# RevA.net
KiCad netlist of a schematic drawn in EAGLE
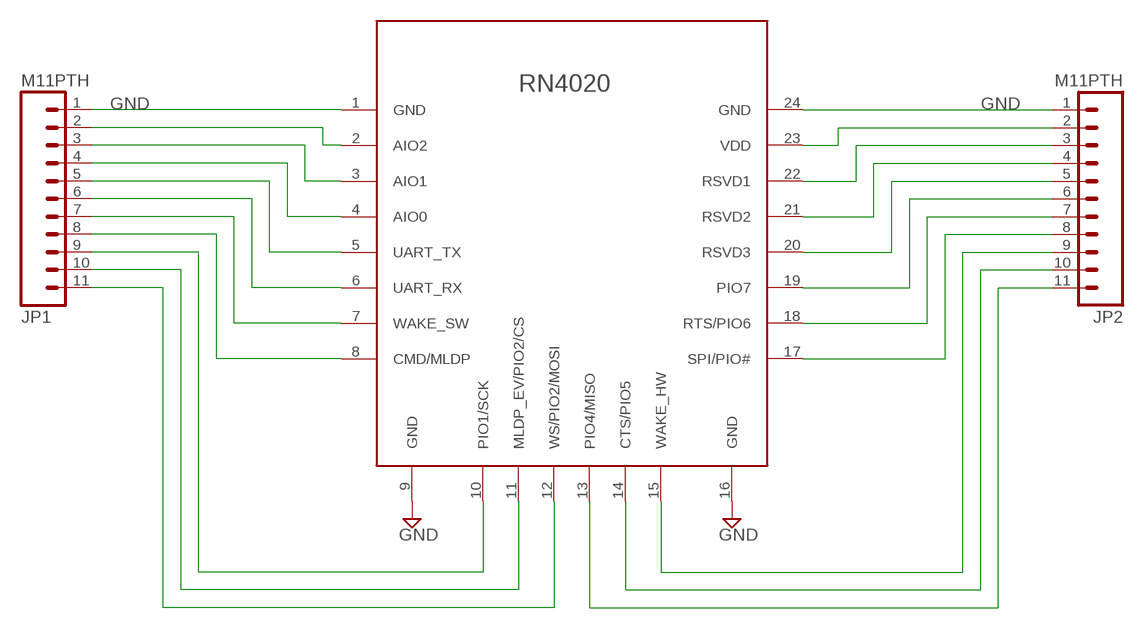
[diagram p0: schematic, sheet 1]

(export (version "E")
  (design (tool "Eeschema 10.0.6"))
  (components
    (comp (ref "JP1")
      (value "M11PTH")
      (footprint "eagle-import:1X11")
      (libsource (lib "eagle-import") (part "M11PTH"))
    )
    (comp (ref "JP2")
      (value "M11PTH")
      (footprint "eagle-import:1X11")
      (libsource (lib "eagle-import") (part "M11PTH"))
    )
    (comp (ref "U$1")
      (value "RN4020")
      (footprint "eagle-import:RN4020")
      (libsource (lib "eagle-import") (part "RN4020"))
    )
  )
  (nets
    (net (code "1") (name "GND") (class "Default")
      (node (ref "JP1") (pin "1") (pinfunction "1_1") (pintype "passive"))
      (node (ref "JP2") (pin "1") (pinfunction "1_1") (pintype "passive"))
      (node (ref "U$1") (pin "1") (pinfunction "GND_1") (pintype "power_in"))
      (node (ref "U$1") (pin "16") (pinfunction "GND_16") (pintype "power_in"))
      (node (ref "U$1") (pin "24") (pinfunction "GND_24") (pintype "power_in"))
      (node (ref "U$1") (pin "9") (pinfunction "GND_9") (pintype "power_in"))
    )
    (net (code "2") (name "Net-(U$1-AIO0)") (class "Default")
      (node (ref "JP1") (pin "4") (pinfunction "4_4") (pintype "passive"))
      (node (ref "U$1") (pin "4") (pinfunction "AIO0_4") (pintype "bidirectional"))
    )
    (net (code "3") (name "Net-(U$1-AIO1)") (class "Default")
      (node (ref "JP1") (pin "3") (pinfunction "3_3") (pintype "passive"))
      (node (ref "U$1") (pin "3") (pinfunction "AIO1_3") (pintype "bidirectional"))
    )
    (net (code "4") (name "Net-(U$1-AIO2)") (class "Default")
      (node (ref "JP1") (pin "2") (pinfunction "2_2") (pintype "passive"))
      (node (ref "U$1") (pin "2") (pinfunction "AIO2_2") (pintype "bidirectional"))
    )
    (net (code "5") (name "Net-(U$1-CMD{slash}MLDP)") (class "Default")
      (node (ref "JP1") (pin "8") (pinfunction "8_8") (pintype "passive"))
      (node (ref "U$1") (pin "8") (pinfunction "CMD/MLDP_8") (pintype "bidirectional"))
    )
    (net (code "6") (name "Net-(U$1-CTS{slash}PIO5)") (class "Default")
      (node (ref "JP2") (pin "10") (pinfunction "10_10") (pintype "passive"))
      (node (ref "U$1") (pin "14") (pinfunction "CTS/PIO5_14") (pintype "bidirectional"))
    )
    (net (code "7") (name "Net-(U$1-MLDP_EV{slash}PIO2{slash}CS)") (class "Default")
      (node (ref "JP1") (pin "10") (pinfunction "10_10") (pintype "passive"))
      (node (ref "U$1") (pin "11") (pinfunction "MLDP_EV/PIO2/CS_11") (pintype "bidirectional"))
    )
    (net (code "8") (name "Net-(U$1-PIO1{slash}SCK)") (class "Default")
      (node (ref "JP1") (pin "9") (pinfunction "9_9") (pintype "passive"))
      (node (ref "U$1") (pin "10") (pinfunction "PIO1/SCK_10") (pintype "bidirectional"))
    )
    (net (code "9") (name "Net-(U$1-PIO4{slash}MISO)") (class "Default")
      (node (ref "JP2") (pin "11") (pinfunction "11_11") (pintype "passive"))
      (node (ref "U$1") (pin "13") (pinfunction "PIO4/MISO_13") (pintype "bidirectional"))
    )
    (net (code "10") (name "Net-(U$1-PIO7)") (class "Default")
      (node (ref "JP2") (pin "6") (pinfunction "6_6") (pintype "passive"))
      (node (ref "U$1") (pin "19") (pinfunction "PIO7_19") (pintype "bidirectional"))
    )
    (net (code "11") (name "Net-(U$1-RSVD1)") (class "Default")
      (node (ref "JP2") (pin "3") (pinfunction "3_3") (pintype "passive"))
      (node (ref "U$1") (pin "22") (pinfunction "RSVD1_22") (pintype "bidirectional"))
    )
    (net (code "12") (name "Net-(U$1-RSVD2)") (class "Default")
      (node (ref "JP2") (pin "4") (pinfunction "4_4") (pintype "passive"))
      (node (ref "U$1") (pin "21") (pinfunction "RSVD2_21") (pintype "bidirectional"))
    )
    (net (code "13") (name "Net-(U$1-RSVD3)") (class "Default")
      (node (ref "JP2") (pin "5") (pinfunction "5_5") (pintype "passive"))
      (node (ref "U$1") (pin "20") (pinfunction "RSVD3_20") (pintype "bidirectional"))
    )
    (net (code "14") (name "Net-(U$1-RTS{slash}PIO6)") (class "Default")
      (node (ref "JP2") (pin "7") (pinfunction "7_7") (pintype "passive"))
      (node (ref "U$1") (pin "18") (pinfunction "RTS/PIO6_18") (pintype "bidirectional"))
    )
    (net (code "15") (name "Net-(U$1-SPI{slash}PIO#)") (class "Default")
      (node (ref "JP2") (pin "8") (pinfunction "8_8") (pintype "passive"))
      (node (ref "U$1") (pin "17") (pinfunction "SPI/PIO#_17") (pintype "bidirectional"))
    )
    (net (code "16") (name "Net-(U$1-UART_RX)") (class "Default")
      (node (ref "JP1") (pin "6") (pinfunction "6_6") (pintype "passive"))
      (node (ref "U$1") (pin "6") (pinfunction "UART_RX_6") (pintype "bidirectional"))
    )
    (net (code "17") (name "Net-(U$1-UART_TX)") (class "Default")
      (node (ref "JP1") (pin "5") (pinfunction "5_5") (pintype "passive"))
      (node (ref "U$1") (pin "5") (pinfunction "UART_TX_5") (pintype "bidirectional"))
    )
    (net (code "18") (name "Net-(U$1-VDD)") (class "Default")
      (node (ref "JP2") (pin "2") (pinfunction "2_2") (pintype "passive"))
      (node (ref "U$1") (pin "23") (pinfunction "VDD_23") (pintype "power_in"))
    )
    (net (code "19") (name "Net-(U$1-WAKE_HW)") (class "Default")
      (node (ref "JP2") (pin "9") (pinfunction "9_9") (pintype "passive"))
      (node (ref "U$1") (pin "15") (pinfunction "WAKE_HW_15") (pintype "bidirectional"))
    )
    (net (code "20") (name "Net-(U$1-WAKE_SW)") (class "Default")
      (node (ref "JP1") (pin "7") (pinfunction "7_7") (pintype "passive"))
      (node (ref "U$1") (pin "7") (pinfunction "WAKE_SW_7") (pintype "bidirectional"))
    )
    (net (code "21") (name "Net-(U$1-WS{slash}PIO2{slash}MOSI)") (class "Default")
      (node (ref "JP1") (pin "11") (pinfunction "11_11") (pintype "passive"))
      (node (ref "U$1") (pin "12") (pinfunction "WS/PIO2/MOSI_12") (pintype "bidirectional"))
    )
  )
)
